# SMI_Link_7-12.net
KiCad netlist of a schematic drawn in Altium Designer
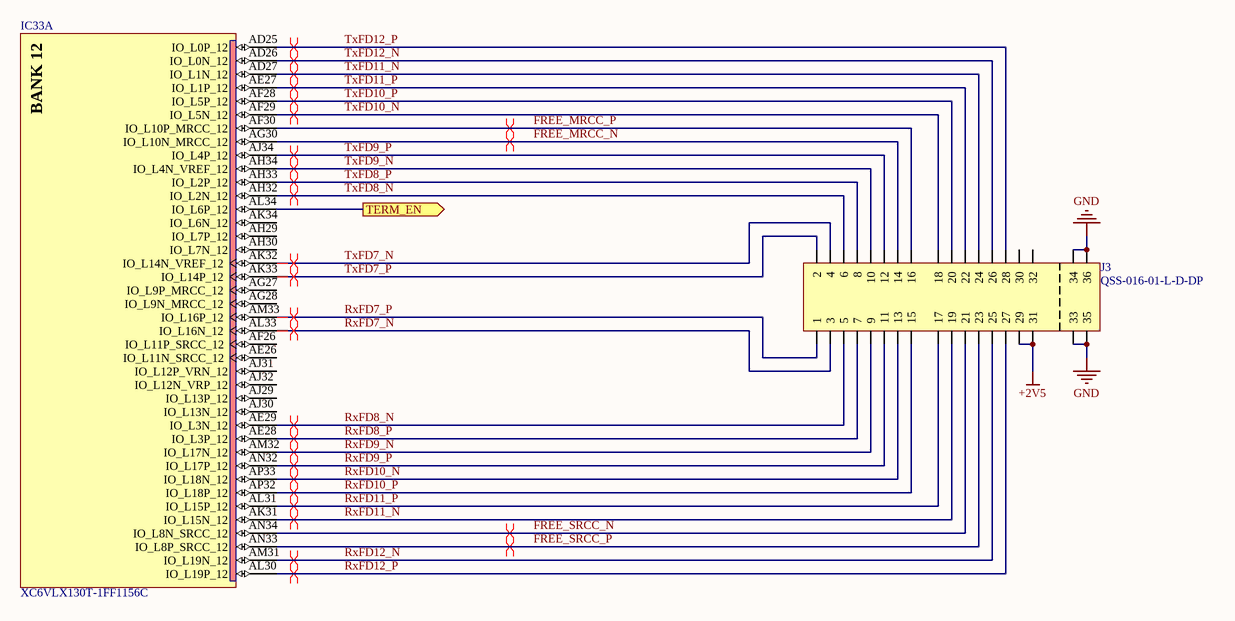
[diagram p0: SMI_Link_7-12.SchDoc]

(export (version "E")
  (design (tool "Eeschema 10.0.6"))
  (components
    (comp (ref "IC33")
      (value "XC6VLX130T-1FF1156C")
      (footprint "FF1156")
      (fields (field (name "PUBLISHER") "Altium Limited"))
      (libsource (lib "Xilinx Virtex-6") (part "XC6VLX130T-1FF1156C"))
    )
    (comp (ref "J3")
      (value "QSS-016-01-L-D-DP")
      (footprint "QSS-016-01-X-D-DP-A")
      (libsource (lib "wr_switch") (part "QSS-016-01-L-D-DP"))
    )
  )
  (nets
    (net (code "1") (name "+2V5") (class "Default")
      (node (ref "J3") (pin "29") (pinfunction "29_29") (pintype "passive"))
      (node (ref "J3") (pin "31") (pinfunction "31_31") (pintype "passive"))
    )
    (net (code "2") (name "/FREE_MRCC_N") (class "Default")
      (node (ref "IC33") (pin "AG30") (pinfunction "IO_L10N_MRCC_12_AG30") (pintype "bidirectional"))
      (node (ref "J3") (pin "14") (pinfunction "14_14") (pintype "passive"))
    )
    (net (code "3") (name "/FREE_MRCC_P") (class "Default")
      (node (ref "IC33") (pin "AF30") (pinfunction "IO_L10P_MRCC_12_AF30") (pintype "bidirectional"))
      (node (ref "J3") (pin "16") (pinfunction "16_16") (pintype "passive"))
    )
    (net (code "4") (name "/FREE_SRCC_N") (class "Default")
      (node (ref "IC33") (pin "AN34") (pinfunction "IO_L8N_SRCC_12_AN34") (pintype "bidirectional"))
      (node (ref "J3") (pin "21") (pinfunction "21_21") (pintype "passive"))
    )
    (net (code "5") (name "/FREE_SRCC_P") (class "Default")
      (node (ref "IC33") (pin "AN33") (pinfunction "IO_L8P_SRCC_12_AN33") (pintype "bidirectional"))
      (node (ref "J3") (pin "23") (pinfunction "23_23") (pintype "passive"))
    )
    (net (code "6") (name "/RxFD7_N") (class "Default")
      (node (ref "IC33") (pin "AL33") (pinfunction "IO_L16N_12_AL33") (pintype "bidirectional"))
      (node (ref "J3") (pin "3") (pinfunction "3_3") (pintype "passive"))
    )
    (net (code "7") (name "/RxFD7_P") (class "Default")
      (node (ref "IC33") (pin "AM33") (pinfunction "IO_L16P_12_AM33") (pintype "bidirectional"))
      (node (ref "J3") (pin "1") (pinfunction "1_1") (pintype "passive"))
    )
    (net (code "8") (name "/RxFD8_N") (class "Default")
      (node (ref "IC33") (pin "AE29") (pinfunction "IO_L3N_12_AE29") (pintype "bidirectional"))
      (node (ref "J3") (pin "5") (pinfunction "5_5") (pintype "passive"))
    )
    (net (code "9") (name "/RxFD8_P") (class "Default")
      (node (ref "IC33") (pin "AE28") (pinfunction "IO_L3P_12_AE28") (pintype "bidirectional"))
      (node (ref "J3") (pin "7") (pinfunction "7_7") (pintype "passive"))
    )
    (net (code "10") (name "/RxFD9_N") (class "Default")
      (node (ref "IC33") (pin "AM32") (pinfunction "IO_L17N_12_AM32") (pintype "bidirectional"))
      (node (ref "J3") (pin "9") (pinfunction "9_9") (pintype "passive"))
    )
    (net (code "11") (name "/RxFD9_P") (class "Default")
      (node (ref "IC33") (pin "AN32") (pinfunction "IO_L17P_12_AN32") (pintype "bidirectional"))
      (node (ref "J3") (pin "11") (pinfunction "11_11") (pintype "passive"))
    )
    (net (code "12") (name "/RxFD10_N") (class "Default")
      (node (ref "IC33") (pin "AP33") (pinfunction "IO_L18N_12_AP33") (pintype "bidirectional"))
      (node (ref "J3") (pin "13") (pinfunction "13_13") (pintype "passive"))
    )
    (net (code "13") (name "/RxFD10_P") (class "Default")
      (node (ref "IC33") (pin "AP32") (pinfunction "IO_L18P_12_AP32") (pintype "bidirectional"))
      (node (ref "J3") (pin "15") (pinfunction "15_15") (pintype "passive"))
    )
    (net (code "14") (name "/RxFD11_N") (class "Default")
      (node (ref "IC33") (pin "AK31") (pinfunction "IO_L15N_12_AK31") (pintype "bidirectional"))
      (node (ref "J3") (pin "19") (pinfunction "19_19") (pintype "passive"))
    )
    (net (code "15") (name "/RxFD11_P") (class "Default")
      (node (ref "IC33") (pin "AL31") (pinfunction "IO_L15P_12_AL31") (pintype "bidirectional"))
      (node (ref "J3") (pin "17") (pinfunction "17_17") (pintype "passive"))
    )
    (net (code "16") (name "/RxFD12_N") (class "Default")
      (node (ref "IC33") (pin "AM31") (pinfunction "IO_L19N_12_AM31") (pintype "bidirectional"))
      (node (ref "J3") (pin "25") (pinfunction "25_25") (pintype "passive"))
    )
    (net (code "17") (name "/RxFD12_P") (class "Default")
      (node (ref "IC33") (pin "AL30") (pinfunction "IO_L19P_12_AL30") (pintype "bidirectional"))
      (node (ref "J3") (pin "27") (pinfunction "27_27") (pintype "passive"))
    )
    (net (code "18") (name "/TERM_EN") (class "Default")
      (node (ref "IC33") (pin "AL34") (pinfunction "IO_L6P_12_AL34") (pintype "bidirectional"))
    )
    (net (code "19") (name "/TxFD7_N") (class "Default")
      (node (ref "IC33") (pin "AK32") (pinfunction "IO_L14N_VREF_12_AK32") (pintype "bidirectional"))
      (node (ref "J3") (pin "4") (pinfunction "4_4") (pintype "passive"))
    )
    (net (code "20") (name "/TxFD7_P") (class "Default")
      (node (ref "IC33") (pin "AK33") (pinfunction "IO_L14P_12_AK33") (pintype "bidirectional"))
      (node (ref "J3") (pin "2") (pinfunction "2_2") (pintype "passive"))
    )
    (net (code "21") (name "/TxFD8_N") (class "Default")
      (node (ref "IC33") (pin "AH32") (pinfunction "IO_L2N_12_AH32") (pintype "bidirectional"))
      (node (ref "J3") (pin "6") (pinfunction "6_6") (pintype "passive"))
    )
    (net (code "22") (name "/TxFD8_P") (class "Default")
      (node (ref "IC33") (pin "AH33") (pinfunction "IO_L2P_12_AH33") (pintype "bidirectional"))
      (node (ref "J3") (pin "8") (pinfunction "8_8") (pintype "passive"))
    )
    (net (code "23") (name "/TxFD9_N") (class "Default")
      (node (ref "IC33") (pin "AH34") (pinfunction "IO_L4N_VREF_12_AH34") (pintype "bidirectional"))
      (node (ref "J3") (pin "10") (pinfunction "10_10") (pintype "passive"))
    )
    (net (code "24") (name "/TxFD9_P") (class "Default")
      (node (ref "IC33") (pin "AJ34") (pinfunction "IO_L4P_12_AJ34") (pintype "bidirectional"))
      (node (ref "J3") (pin "12") (pinfunction "12_12") (pintype "passive"))
    )
    (net (code "25") (name "/TxFD10_N") (class "Default")
      (node (ref "IC33") (pin "AF29") (pinfunction "IO_L5N_12_AF29") (pintype "bidirectional"))
      (node (ref "J3") (pin "18") (pinfunction "18_18") (pintype "passive"))
    )
    (net (code "26") (name "/TxFD10_P") (class "Default")
      (node (ref "IC33") (pin "AF28") (pinfunction "IO_L5P_12_AF28") (pintype "bidirectional"))
      (node (ref "J3") (pin "20") (pinfunction "20_20") (pintype "passive"))
    )
    (net (code "27") (name "/TxFD11_N") (class "Default")
      (node (ref "IC33") (pin "AD27") (pinfunction "IO_L1N_12_AD27") (pintype "bidirectional"))
      (node (ref "J3") (pin "24") (pinfunction "24_24") (pintype "passive"))
    )
    (net (code "28") (name "/TxFD11_P") (class "Default")
      (node (ref "IC33") (pin "AE27") (pinfunction "IO_L1P_12_AE27") (pintype "bidirectional"))
      (node (ref "J3") (pin "22") (pinfunction "22_22") (pintype "passive"))
    )
    (net (code "29") (name "/TxFD12_N") (class "Default")
      (node (ref "IC33") (pin "AD26") (pinfunction "IO_L0N_12_AD26") (pintype "bidirectional"))
      (node (ref "J3") (pin "26") (pinfunction "26_26") (pintype "passive"))
    )
    (net (code "30") (name "/TxFD12_P") (class "Default")
      (node (ref "IC33") (pin "AD25") (pinfunction "IO_L0P_12_AD25") (pintype "bidirectional"))
      (node (ref "J3") (pin "28") (pinfunction "28_28") (pintype "passive"))
    )
    (net (code "31") (name "GND") (class "Default")
      (node (ref "J3") (pin "33") (pinfunction "33_33") (pintype "passive"))
      (node (ref "J3") (pin "34") (pinfunction "34_34") (pintype "passive"))
      (node (ref "J3") (pin "35") (pinfunction "35_35") (pintype "passive"))
      (node (ref "J3") (pin "36") (pinfunction "36_36") (pintype "passive"))
    )
    (net (code "32") (name "unconnected-(IC33A-IO_L6N_12-PadAK34)") (class "Default")
      (node (ref "IC33") (pin "AK34") (pinfunction "IO_L6N_12_AK34") (pintype "bidirectional"))
    )
    (net (code "33") (name "unconnected-(IC33A-IO_L7N_12-PadAH30)") (class "Default")
      (node (ref "IC33") (pin "AH30") (pinfunction "IO_L7N_12_AH30") (pintype "bidirectional"))
    )
    (net (code "34") (name "unconnected-(IC33A-IO_L7P_12-PadAH29)") (class "Default")
      (node (ref "IC33") (pin "AH29") (pinfunction "IO_L7P_12_AH29") (pintype "bidirectional"))
    )
    (net (code "35") (name "unconnected-(IC33A-IO_L9N_MRCC_12-PadAG28)") (class "Default")
      (node (ref "IC33") (pin "AG28") (pinfunction "IO_L9N_MRCC_12_AG28") (pintype "bidirectional"))
    )
    (net (code "36") (name "unconnected-(IC33A-IO_L9P_MRCC_12-PadAG27)") (class "Default")
      (node (ref "IC33") (pin "AG27") (pinfunction "IO_L9P_MRCC_12_AG27") (pintype "bidirectional"))
    )
    (net (code "37") (name "unconnected-(IC33A-IO_L11N_SRCC_12-PadAE26)") (class "Default")
      (node (ref "IC33") (pin "AE26") (pinfunction "IO_L11N_SRCC_12_AE26") (pintype "bidirectional"))
    )
    (net (code "38") (name "unconnected-(IC33A-IO_L11P_SRCC_12-PadAF26)") (class "Default")
      (node (ref "IC33") (pin "AF26") (pinfunction "IO_L11P_SRCC_12_AF26") (pintype "bidirectional"))
    )
    (net (code "39") (name "unconnected-(IC33A-IO_L12N_VRP_12-PadAJ32)") (class "Default")
      (node (ref "IC33") (pin "AJ32") (pinfunction "IO_L12N_VRP_12_AJ32") (pintype "bidirectional"))
    )
    (net (code "40") (name "unconnected-(IC33A-IO_L12P_VRN_12-PadAJ31)") (class "Default")
      (node (ref "IC33") (pin "AJ31") (pinfunction "IO_L12P_VRN_12_AJ31") (pintype "bidirectional"))
    )
    (net (code "41") (name "unconnected-(IC33A-IO_L13N_12-PadAJ30)") (class "Default")
      (node (ref "IC33") (pin "AJ30") (pinfunction "IO_L13N_12_AJ30") (pintype "bidirectional"))
    )
    (net (code "42") (name "unconnected-(IC33A-IO_L13P_12-PadAJ29)") (class "Default")
      (node (ref "IC33") (pin "AJ29") (pinfunction "IO_L13P_12_AJ29") (pintype "bidirectional"))
    )
    (net (code "43") (name "unconnected-(J3-Pad30)") (class "Default")
      (node (ref "J3") (pin "30") (pinfunction "30_30") (pintype "passive"))
    )
    (net (code "44") (name "unconnected-(J3-Pad32)") (class "Default")
      (node (ref "J3") (pin "32") (pinfunction "32_32") (pintype "passive"))
    )
  )
)
